# SMD_Switch_v01.net
KiCad netlist of a schematic drawn in EAGLE
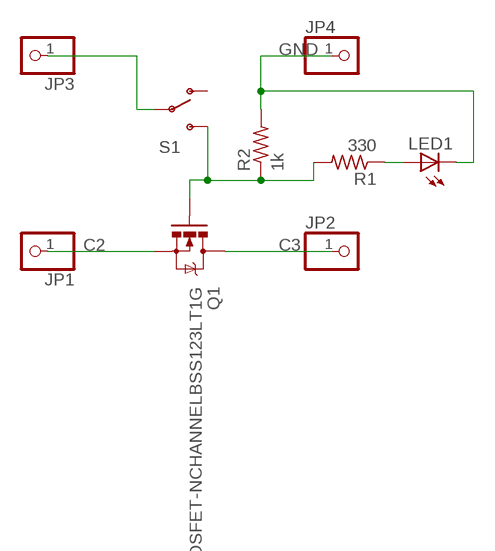
[diagram p0: schematic, sheet 1]

(export (version "E")
  (design (tool "Eeschema 10.0.6"))
  (components
    (comp (ref "JP1")
      (value "PINHD-1X1")
      (footprint "eagle-import:1X01")
      (libsource (lib "eagle-import") (part "PINHD-1X1"))
    )
    (comp (ref "JP2")
      (value "PINHD-1X1")
      (footprint "eagle-import:1X01")
      (libsource (lib "eagle-import") (part "PINHD-1X1"))
    )
    (comp (ref "JP3")
      (value "PINHD-1X1")
      (footprint "eagle-import:1X01")
      (libsource (lib "eagle-import") (part "PINHD-1X1"))
    )
    (comp (ref "JP4")
      (value "PINHD-1X1")
      (footprint "eagle-import:1X01")
      (libsource (lib "eagle-import") (part "PINHD-1X1"))
    )
    (comp (ref "LED1")
      (value "LEDCHIP-LED0603")
      (footprint "eagle-import:CHIP-LED0603")
      (libsource (lib "eagle-import") (part "LEDCHIP-LED0603"))
    )
    (comp (ref "Q1")
      (value "MOSFET-NCHANNELBSS123LT1G")
      (footprint "eagle-import:SOT23")
      (libsource (lib "eagle-import") (part "MOSFET-NCHANNELBSS123LT1G"))
    )
    (comp (ref "R1")
      (value "330")
      (footprint "eagle-import:R0402")
      (libsource (lib "eagle-import") (part "R-US_R0402"))
    )
    (comp (ref "R2")
      (value "1k")
      (footprint "eagle-import:R0402")
      (libsource (lib "eagle-import") (part "R-US_R0402"))
    )
    (comp (ref "S1")
      (value "SWITCH-SPDT-SMD-A")
      (footprint "eagle-import:SWITCH-SPST-SMD-A")
      (libsource (lib "eagle-import") (part "SWITCH-SPDT-SMD-A"))
    )
  )
  (nets
    (net (code "1") (name "/C2") (class "Default")
      (node (ref "JP1") (pin "1") (pinfunction "1_1") (pintype "passive"))
      (node (ref "Q1") (pin "2") (pinfunction "S_2") (pintype "passive"))
    )
    (net (code "2") (name "/C3") (class "Default")
      (node (ref "JP2") (pin "1") (pinfunction "1_1") (pintype "passive"))
      (node (ref "Q1") (pin "3") (pinfunction "D_3") (pintype "passive"))
    )
    (net (code "3") (name "/GND") (class "Default")
      (node (ref "JP4") (pin "1") (pinfunction "1_1") (pintype "passive"))
      (node (ref "LED1") (pin "C") (pinfunction "C_C") (pintype "passive"))
      (node (ref "R2") (pin "2") (pinfunction "2_2") (pintype "passive"))
    )
    (net (code "4") (name "Net-(LED1-PadA)") (class "Default")
      (node (ref "LED1") (pin "A") (pinfunction "A_A") (pintype "passive"))
      (node (ref "R1") (pin "1") (pinfunction "1_1") (pintype "passive"))
    )
    (net (code "5") (name "Net-(Q1-G)") (class "Default")
      (node (ref "Q1") (pin "1") (pinfunction "G_1") (pintype "passive"))
      (node (ref "R1") (pin "2") (pinfunction "2_2") (pintype "passive"))
      (node (ref "R2") (pin "1") (pinfunction "1_1") (pintype "passive"))
      (node (ref "S1") (pin "3") (pinfunction "S_3") (pintype "passive"))
    )
    (net (code "6") (name "Net-(S1-P)") (class "Default")
      (node (ref "JP3") (pin "1") (pinfunction "1_1") (pintype "passive"))
      (node (ref "S1") (pin "2") (pinfunction "P_2") (pintype "passive"))
    )
    (net (code "7") (name "unconnected-(S1-O-Pad1)") (class "Default")
      (node (ref "S1") (pin "1") (pinfunction "O_1") (pintype "passive"))
    )
  )
)
